# weather.net
KiCad netlist of a schematic drawn in EAGLE
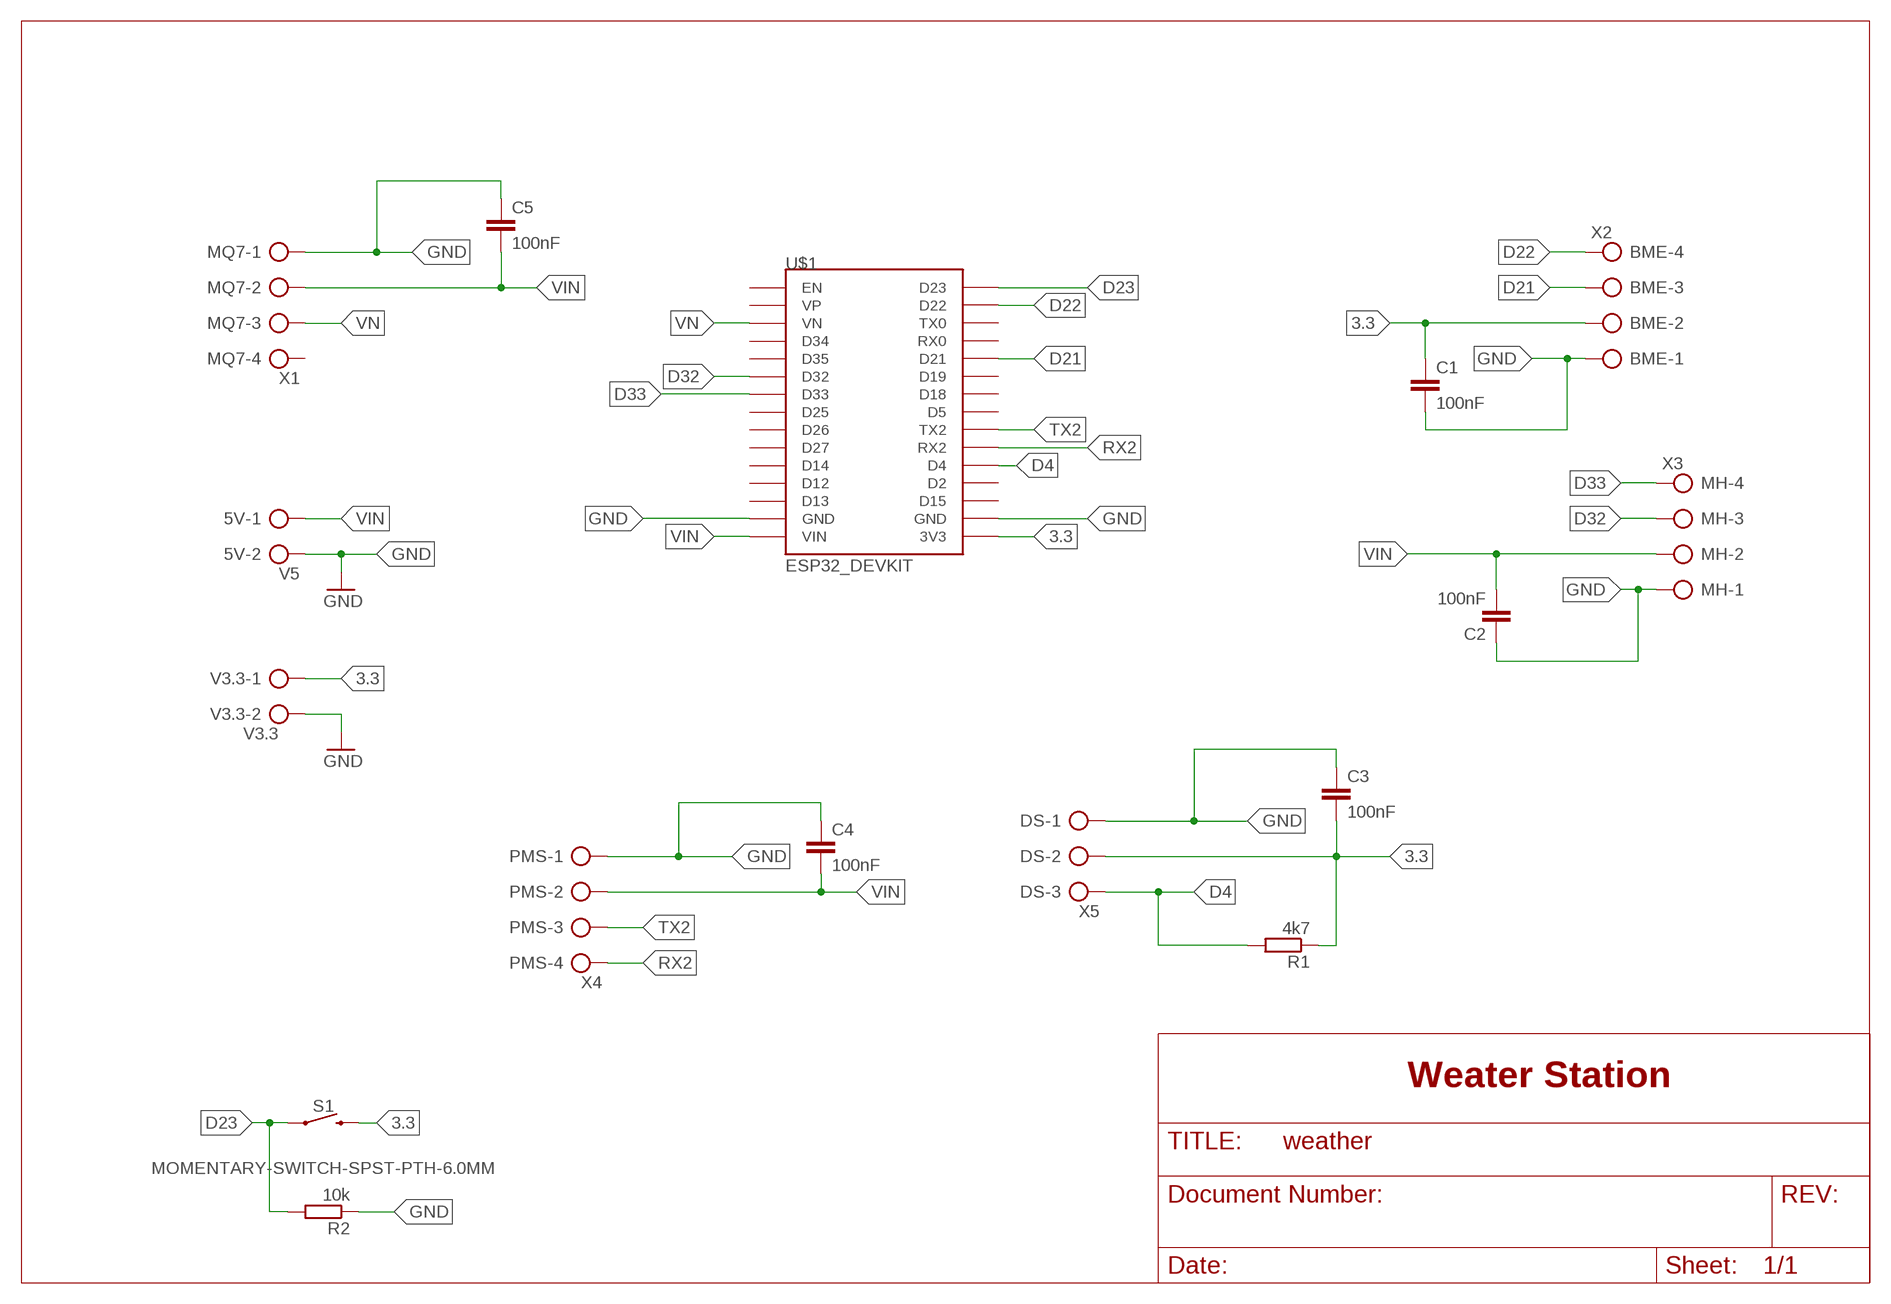
[diagram p0: schematic, sheet 1]

(export (version "E")
  (design (tool "Eeschema 10.0.6"))
  (components
    (comp (ref "5V")
      (value "V5")
      (footprint "eagle-import:AK500_2-H")
      (libsource (lib "eagle-import") (part "AK500/2-H"))
    )
    (comp (ref "BME")
      (value "X2")
      (footprint "eagle-import:AK500_4-H")
      (libsource (lib "eagle-import") (part "AK500/4-H"))
    )
    (comp (ref "C1")
      (value "100nF")
      (footprint "eagle-import:C050-025X075")
      (libsource (lib "eagle-import") (part "C-EU050-025X075"))
    )
    (comp (ref "C2")
      (value "100nF")
      (footprint "eagle-import:C050-025X075")
      (libsource (lib "eagle-import") (part "C-EU050-025X075"))
    )
    (comp (ref "C3")
      (value "100nF")
      (footprint "eagle-import:C050-025X075")
      (libsource (lib "eagle-import") (part "C-EU050-025X075"))
    )
    (comp (ref "C4")
      (value "100nF")
      (footprint "eagle-import:C050-025X075")
      (libsource (lib "eagle-import") (part "C-EU050-025X075"))
    )
    (comp (ref "C5")
      (value "100nF")
      (footprint "eagle-import:C050-025X075")
      (libsource (lib "eagle-import") (part "C-EU050-025X075"))
    )
    (comp (ref "DS")
      (value "X5")
      (footprint "eagle-import:AK500_3-H")
      (libsource (lib "eagle-import") (part "AK500/3-H"))
    )
    (comp (ref "MH")
      (value "X3")
      (footprint "eagle-import:AK500_4-H")
      (libsource (lib "eagle-import") (part "AK500/4-H"))
    )
    (comp (ref "MQ7")
      (value "X1")
      (footprint "eagle-import:AK500_4-H")
      (libsource (lib "eagle-import") (part "AK500/4-H"))
    )
    (comp (ref "PMS")
      (value "X4")
      (footprint "eagle-import:AK500_4-H")
      (libsource (lib "eagle-import") (part "AK500/4-H"))
    )
    (comp (ref "R1")
      (value "4k7")
      (footprint "eagle-import:0207_10")
      (libsource (lib "eagle-import") (part "R-EU_0207/10"))
    )
    (comp (ref "R2")
      (value "10k")
      (footprint "eagle-import:0207_10")
      (libsource (lib "eagle-import") (part "R-EU_0207/10"))
    )
    (comp (ref "S1")
      (value "MOMENTARY-SWITCH-SPST-PTH-6.0MM")
      (footprint "eagle-import:TACTILE_SWITCH_PTH_6.0MM")
      (libsource (lib "eagle-import") (part "MOMENTARY-SWITCH-SPST-PTH-6.0MM"))
    )
    (comp (ref "U$1")
      (value "ESP32_DEVKIT")
      (footprint "eagle-import:ESP32_DEVKIT")
      (libsource (lib "eagle-import") (part "ESP32_DEVKIT"))
    )
    (comp (ref "V3.3")
      (value "V3.3")
      (footprint "eagle-import:AK500_2-H")
      (libsource (lib "eagle-import") (part "AK500/2-H"))
    )
  )
  (nets
    (net (code "1") (name "3.3") (class "Default")
      (node (ref "BME") (pin "2") (pinfunction "KL_2") (pintype "passive"))
      (node (ref "C1") (pin "1") (pinfunction "1_1") (pintype "passive"))
      (node (ref "C3") (pin "2") (pinfunction "2_2") (pintype "passive"))
      (node (ref "DS") (pin "2") (pinfunction "KL_2") (pintype "passive"))
      (node (ref "R1") (pin "1") (pinfunction "1_1") (pintype "passive"))
      (node (ref "S1") (pin "3") (pinfunction "2_3") (pintype "passive"))
      (node (ref "U$1") (pin "3V3") (pinfunction "3V3_3V3") (pintype "bidirectional"))
      (node (ref "V3.3") (pin "1") (pinfunction "KL_1") (pintype "passive"))
    )
    (net (code "2") (name "D4") (class "Default")
      (node (ref "DS") (pin "3") (pinfunction "KL_3") (pintype "passive"))
      (node (ref "R1") (pin "2") (pinfunction "2_2") (pintype "passive"))
      (node (ref "U$1") (pin "D4") (pinfunction "D4_D4") (pintype "bidirectional"))
    )
    (net (code "3") (name "D21") (class "Default")
      (node (ref "BME") (pin "3") (pinfunction "KL_3") (pintype "passive"))
      (node (ref "U$1") (pin "D21") (pinfunction "D21_D21") (pintype "bidirectional"))
    )
    (net (code "4") (name "D22") (class "Default")
      (node (ref "BME") (pin "4") (pinfunction "KL_4") (pintype "passive"))
      (node (ref "U$1") (pin "D22") (pinfunction "D22_D22") (pintype "bidirectional"))
    )
    (net (code "5") (name "D23") (class "Default")
      (node (ref "R2") (pin "2") (pinfunction "2_2") (pintype "passive"))
      (node (ref "S1") (pin "1") (pinfunction "1_1") (pintype "passive"))
      (node (ref "U$1") (pin "D23") (pinfunction "D23_D23") (pintype "bidirectional"))
    )
    (net (code "6") (name "D32") (class "Default")
      (node (ref "MH") (pin "3") (pinfunction "KL_3") (pintype "passive"))
      (node (ref "U$1") (pin "D32") (pinfunction "D32_D32") (pintype "bidirectional"))
    )
    (net (code "7") (name "D33") (class "Default")
      (node (ref "MH") (pin "4") (pinfunction "KL_4") (pintype "passive"))
      (node (ref "U$1") (pin "D33") (pinfunction "D33_D33") (pintype "bidirectional"))
    )
    (net (code "8") (name "GND") (class "Default")
      (node (ref "5V") (pin "2") (pinfunction "KL_2") (pintype "passive"))
      (node (ref "BME") (pin "1") (pinfunction "KL_1") (pintype "passive"))
      (node (ref "C1") (pin "2") (pinfunction "2_2") (pintype "passive"))
      (node (ref "C2") (pin "1") (pinfunction "1_1") (pintype "passive"))
      (node (ref "C3") (pin "1") (pinfunction "1_1") (pintype "passive"))
      (node (ref "C4") (pin "1") (pinfunction "1_1") (pintype "passive"))
      (node (ref "C5") (pin "1") (pinfunction "1_1") (pintype "passive"))
      (node (ref "DS") (pin "1") (pinfunction "KL_1") (pintype "passive"))
      (node (ref "MH") (pin "1") (pinfunction "KL_1") (pintype "passive"))
      (node (ref "MQ7") (pin "1") (pinfunction "KL_1") (pintype "passive"))
      (node (ref "PMS") (pin "1") (pinfunction "KL_1") (pintype "passive"))
      (node (ref "R2") (pin "1") (pinfunction "1_1") (pintype "passive"))
      (node (ref "U$1") (pin "GND@1") (pinfunction "GND_GND@1") (pintype "bidirectional"))
      (node (ref "U$1") (pin "GND@2") (pinfunction "GND_GND@2") (pintype "bidirectional"))
      (node (ref "V3.3") (pin "2") (pinfunction "KL_2") (pintype "passive"))
    )
    (net (code "9") (name "RX2") (class "Default")
      (node (ref "PMS") (pin "4") (pinfunction "KL_4") (pintype "passive"))
      (node (ref "U$1") (pin "RX2") (pinfunction "RX2_RX2") (pintype "bidirectional"))
    )
    (net (code "10") (name "TX2") (class "Default")
      (node (ref "PMS") (pin "3") (pinfunction "KL_3") (pintype "passive"))
      (node (ref "U$1") (pin "TX2") (pinfunction "TX2_TX2") (pintype "bidirectional"))
    )
    (net (code "11") (name "VIN") (class "Default")
      (node (ref "5V") (pin "1") (pinfunction "KL_1") (pintype "passive"))
      (node (ref "C2") (pin "2") (pinfunction "2_2") (pintype "passive"))
      (node (ref "C4") (pin "2") (pinfunction "2_2") (pintype "passive"))
      (node (ref "C5") (pin "2") (pinfunction "2_2") (pintype "passive"))
      (node (ref "MH") (pin "2") (pinfunction "KL_2") (pintype "passive"))
      (node (ref "MQ7") (pin "2") (pinfunction "KL_2") (pintype "passive"))
      (node (ref "PMS") (pin "2") (pinfunction "KL_2") (pintype "passive"))
      (node (ref "U$1") (pin "VIN") (pinfunction "VIN_VIN") (pintype "bidirectional"))
    )
    (net (code "12") (name "VN") (class "Default")
      (node (ref "MQ7") (pin "3") (pinfunction "KL_3") (pintype "passive"))
      (node (ref "U$1") (pin "VN") (pinfunction "VN_VN") (pintype "bidirectional"))
    )
    (net (code "13") (name "unconnected-(MQ7D-KL-Pad4)") (class "Default")
      (node (ref "MQ7") (pin "4") (pinfunction "KL_4") (pintype "passive"))
    )
    (net (code "14") (name "unconnected-(U$1-PadD2)") (class "Default")
      (node (ref "U$1") (pin "D2") (pinfunction "D2_D2") (pintype "bidirectional"))
    )
    (net (code "15") (name "unconnected-(U$1-PadD5)") (class "Default")
      (node (ref "U$1") (pin "D5") (pinfunction "D5_D5") (pintype "bidirectional"))
    )
    (net (code "16") (name "unconnected-(U$1-PadD12)") (class "Default")
      (node (ref "U$1") (pin "D12") (pinfunction "D12_D12") (pintype "bidirectional"))
    )
    (net (code "17") (name "unconnected-(U$1-PadD13)") (class "Default")
      (node (ref "U$1") (pin "D13") (pinfunction "D13_D13") (pintype "bidirectional"))
    )
    (net (code "18") (name "unconnected-(U$1-PadD14)") (class "Default")
      (node (ref "U$1") (pin "D14") (pinfunction "D14_D14") (pintype "bidirectional"))
    )
    (net (code "19") (name "unconnected-(U$1-PadD15)") (class "Default")
      (node (ref "U$1") (pin "D15") (pinfunction "D15_D15") (pintype "bidirectional"))
    )
    (net (code "20") (name "unconnected-(U$1-PadD18)") (class "Default")
      (node (ref "U$1") (pin "D18") (pinfunction "D18_D18") (pintype "bidirectional"))
    )
    (net (code "21") (name "unconnected-(U$1-PadD19)") (class "Default")
      (node (ref "U$1") (pin "D19") (pinfunction "D19_D19") (pintype "bidirectional"))
    )
    (net (code "22") (name "unconnected-(U$1-PadD25)") (class "Default")
      (node (ref "U$1") (pin "D25") (pinfunction "D25_D25") (pintype "bidirectional"))
    )
    (net (code "23") (name "unconnected-(U$1-PadD26)") (class "Default")
      (node (ref "U$1") (pin "D26") (pinfunction "D26_D26") (pintype "bidirectional"))
    )
    (net (code "24") (name "unconnected-(U$1-PadD27)") (class "Default")
      (node (ref "U$1") (pin "D27") (pinfunction "D27_D27") (pintype "bidirectional"))
    )
    (net (code "25") (name "unconnected-(U$1-PadD34)") (class "Default")
      (node (ref "U$1") (pin "D34") (pinfunction "D34_D34") (pintype "bidirectional"))
    )
    (net (code "26") (name "unconnected-(U$1-PadD35)") (class "Default")
      (node (ref "U$1") (pin "D35") (pinfunction "D35_D35") (pintype "bidirectional"))
    )
    (net (code "27") (name "unconnected-(U$1-PadEN)") (class "Default")
      (node (ref "U$1") (pin "EN") (pinfunction "EN_EN") (pintype "bidirectional"))
    )
    (net (code "28") (name "unconnected-(U$1-PadRX0)") (class "Default")
      (node (ref "U$1") (pin "RX0") (pinfunction "RX0_RX0") (pintype "bidirectional"))
    )
    (net (code "29") (name "unconnected-(U$1-PadTX0)") (class "Default")
      (node (ref "U$1") (pin "TX0") (pinfunction "TX0_TX0") (pintype "bidirectional"))
    )
    (net (code "30") (name "unconnected-(U$1-PadVP)") (class "Default")
      (node (ref "U$1") (pin "VP") (pinfunction "VP_VP") (pintype "bidirectional"))
    )
  )
)
